# pro-micro-screw-terminal-v1_0.net
KiCad netlist of a schematic drawn in EAGLE
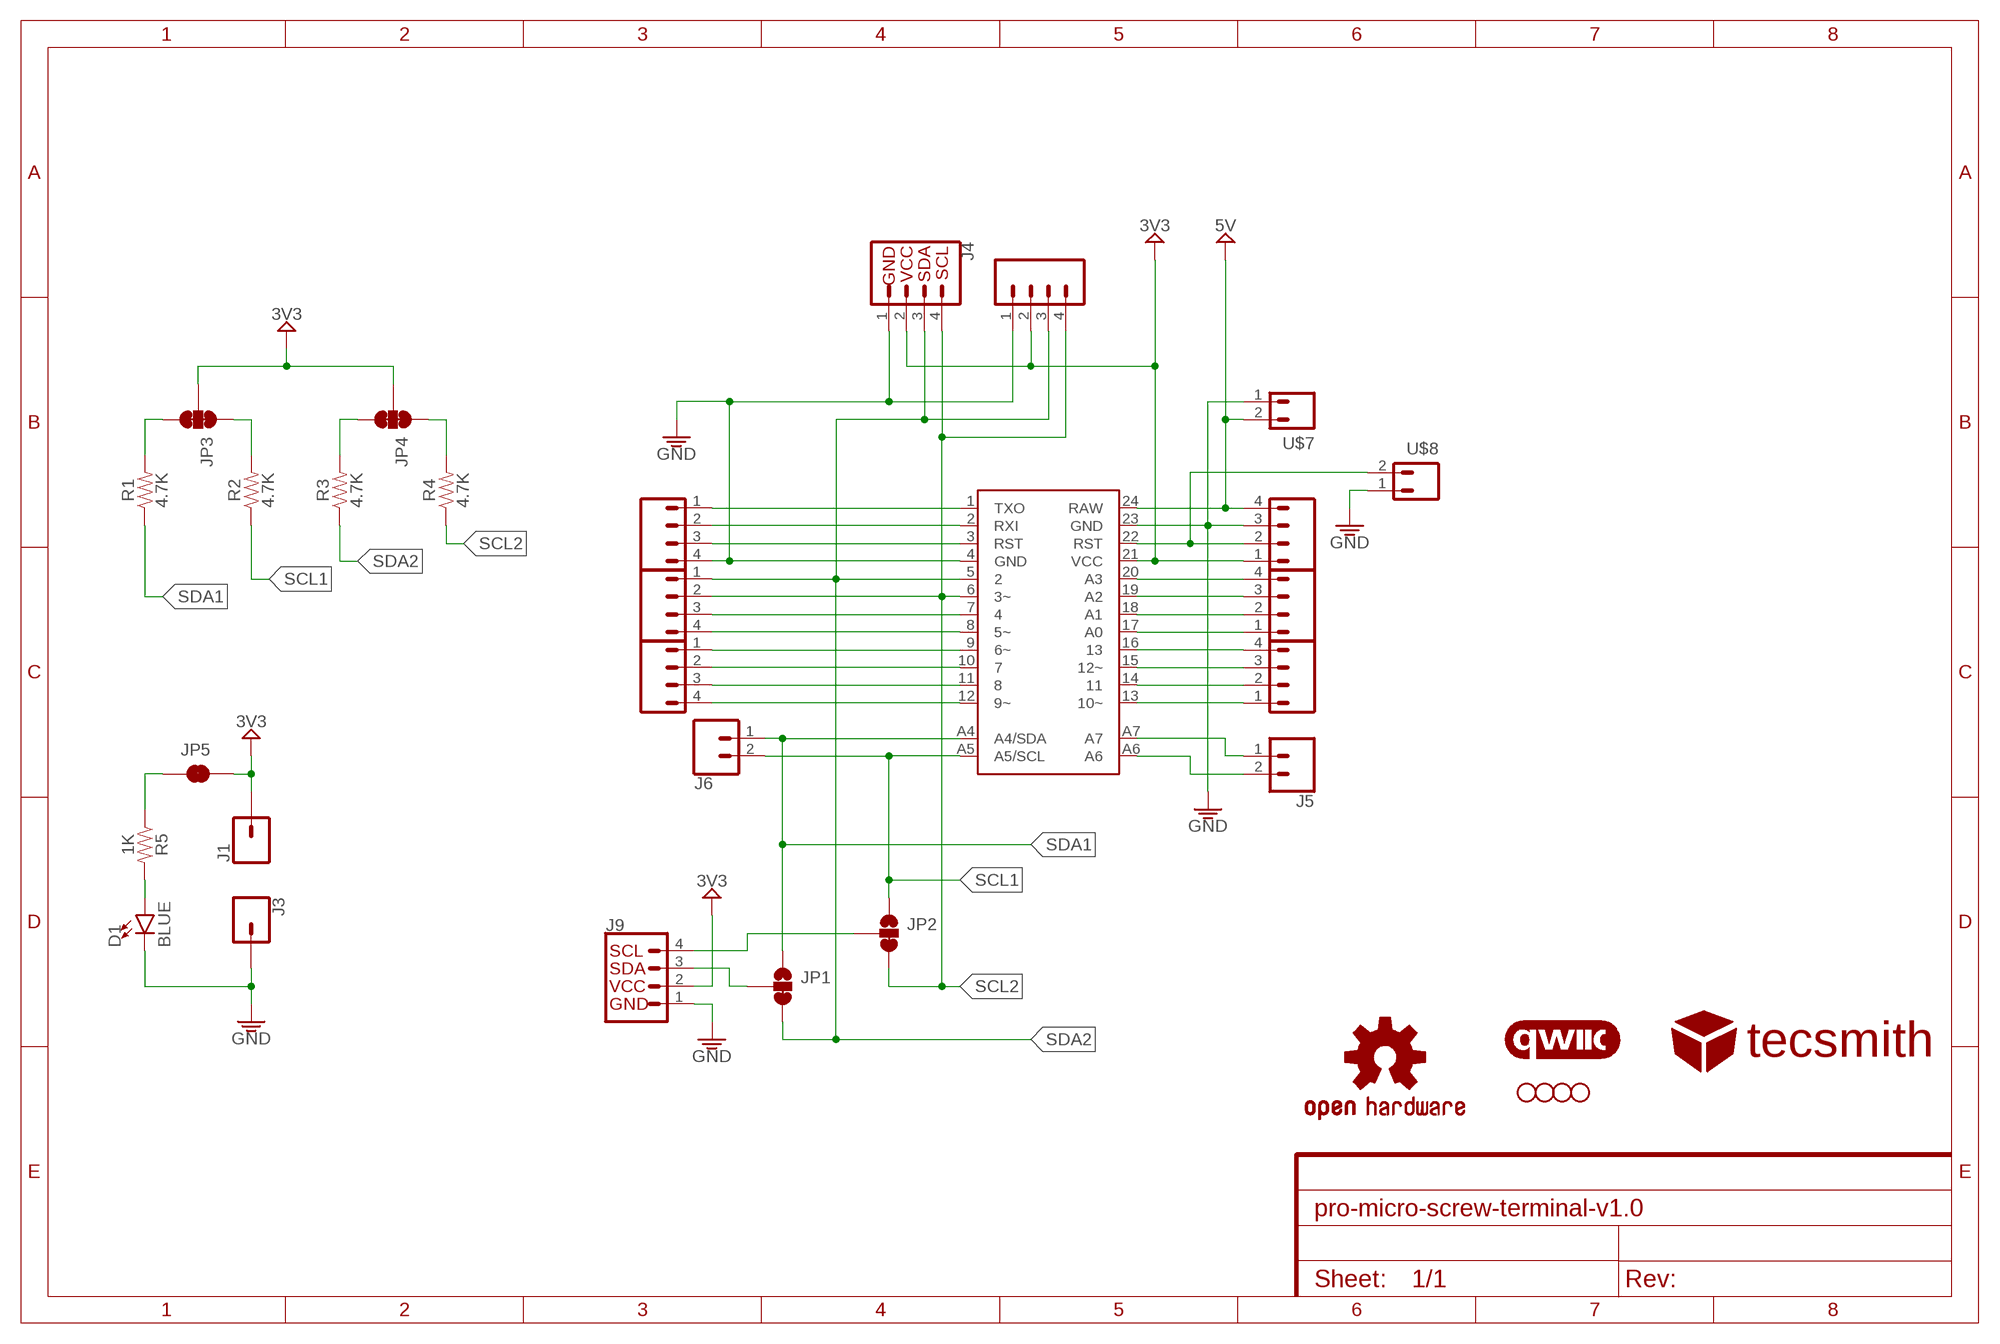
[diagram p0: schematic, sheet 1]

(export (version "E")
  (design (tool "Eeschema 10.0.6"))
  (components
    (comp (ref "B1")
      (value "ARDUINO_PRO_MININO_FTDI")
      (footprint "eagle-import:ARDUINO_PRO_MINI")
      (libsource (lib "eagle-import") (part "ARDUINO_PRO_MININO_FTDI"))
    )
    (comp (ref "D1")
      (value "BLUE")
      (footprint "eagle-import:LED-0603")
      (libsource (lib "eagle-import") (part "LED-BLUE0603"))
    )
    (comp (ref "H1")
      (value "STAND-OFF")
      (footprint "eagle-import:STAND-OFF")
      (libsource (lib "eagle-import") (part "STAND-OFF"))
    )
    (comp (ref "H2")
      (value "STAND-OFF")
      (footprint "eagle-import:STAND-OFF")
      (libsource (lib "eagle-import") (part "STAND-OFF"))
    )
    (comp (ref "H5")
      (value "STAND-OFF")
      (footprint "eagle-import:STAND-OFF")
      (libsource (lib "eagle-import") (part "STAND-OFF"))
    )
    (comp (ref "H6")
      (value "STAND-OFF")
      (footprint "eagle-import:STAND-OFF")
      (libsource (lib "eagle-import") (part "STAND-OFF"))
    )
    (comp (ref "J1")
      (value "CONN_01PTH_NO_SILK_YES_STOP")
      (footprint "eagle-import:1X01_NO_SILK")
      (libsource (lib "eagle-import") (part "CONN_01PTH_NO_SILK_YES_STOP"))
    )
    (comp (ref "J2")
      (value "CONN_04PTH")
      (footprint "eagle-import:1X04")
      (libsource (lib "eagle-import") (part "CONN_04PTH"))
    )
    (comp (ref "J3")
      (value "CONN_01PTH_NO_SILK_YES_STOP")
      (footprint "eagle-import:1X01_NO_SILK")
      (libsource (lib "eagle-import") (part "CONN_01PTH_NO_SILK_YES_STOP"))
    )
    (comp (ref "J4")
      (value "QWIIC_RIGHT_ANGLE")
      (footprint "eagle-import:JST04_1MM_RA")
      (libsource (lib "eagle-import") (part "QWIIC_CONNECTORJS-1MM"))
    )
    (comp (ref "J5")
      (value "CONN_02")
      (footprint "eagle-import:1X02")
      (libsource (lib "eagle-import") (part "CONN_02"))
    )
    (comp (ref "J6")
      (value "CONN_02")
      (footprint "eagle-import:1X02")
      (libsource (lib "eagle-import") (part "CONN_02"))
    )
    (comp (ref "J9")
      (value "QWIIC_RIGHT_ANGLE")
      (footprint "eagle-import:JST04_1MM_RA")
      (libsource (lib "eagle-import") (part "QWIIC_CONNECTORJS-1MM"))
    )
    (comp (ref "JP1")
      (value "JUMPER-SMT_3_1-NC_TRACE_SILK")
      (footprint "eagle-import:SMT-JUMPER_3_1-NC_TRACE_SILK")
      (libsource (lib "eagle-import") (part "JUMPER-SMT_3_1-NC_TRACE_SILK"))
    )
    (comp (ref "JP2")
      (value "JUMPER-SMT_3_1-NC_TRACE_SILK")
      (footprint "eagle-import:SMT-JUMPER_3_1-NC_TRACE_SILK")
      (libsource (lib "eagle-import") (part "JUMPER-SMT_3_1-NC_TRACE_SILK"))
    )
    (comp (ref "JP3")
      (value "JUMPER-SMT_3_2-NC_TRACE_SILK")
      (footprint "eagle-import:SMT-JUMPER_3_2-NC_TRACE_SILK")
      (libsource (lib "eagle-import") (part "JUMPER-SMT_3_2-NC_TRACE_SILK"))
    )
    (comp (ref "JP4")
      (value "JUMPER-SMT_3_2-NC_TRACE_SILK")
      (footprint "eagle-import:SMT-JUMPER_3_2-NC_TRACE_SILK")
      (libsource (lib "eagle-import") (part "JUMPER-SMT_3_2-NC_TRACE_SILK"))
    )
    (comp (ref "JP5")
      (value "JUMPER-SMT_2_NC_TRACE_SILK")
      (footprint "eagle-import:SMT-JUMPER_2_NC_TRACE_SILK")
      (libsource (lib "eagle-import") (part "JUMPER-SMT_2_NC_TRACE_SILK"))
    )
    (comp (ref "LOGO1")
      (value "OSHW-LOGOS")
      (footprint "eagle-import:OSHW-LOGO-S")
      (libsource (lib "eagle-import") (part "OSHW-LOGOS"))
    )
    (comp (ref "LOGO2")
      (value "QWIIC_LOGO_6MM")
      (footprint "eagle-import:QWIIC_6MM")
      (libsource (lib "eagle-import") (part "QWIIC_LOGO_6MM"))
    )
    (comp (ref "R1")
      (value "4.7K")
      (footprint "eagle-import:0805")
      (libsource (lib "eagle-import") (part "RESISTOR0805"))
    )
    (comp (ref "R2")
      (value "4.7K")
      (footprint "eagle-import:0805")
      (libsource (lib "eagle-import") (part "RESISTOR0805"))
    )
    (comp (ref "R3")
      (value "4.7K")
      (footprint "eagle-import:0805")
      (libsource (lib "eagle-import") (part "RESISTOR0805"))
    )
    (comp (ref "R4")
      (value "4.7K")
      (footprint "eagle-import:0805")
      (libsource (lib "eagle-import") (part "RESISTOR0805"))
    )
    (comp (ref "R5")
      (value "1K")
      (footprint "eagle-import:0603")
      (libsource (lib "eagle-import") (part "330OHM-0603-1/10W-1%"))
    )
    (comp (ref "U$1")
      (value "CON_04SCREW")
      (footprint "eagle-import:WURTH_2431_3.5MM_4X_SCREW")
      (libsource (lib "eagle-import") (part "CON_04SCREW"))
    )
    (comp (ref "U$2")
      (value "CON_04SCREW")
      (footprint "eagle-import:WURTH_2431_3.5MM_4X_SCREW")
      (libsource (lib "eagle-import") (part "CON_04SCREW"))
    )
    (comp (ref "U$3")
      (value "CON_04SCREW")
      (footprint "eagle-import:WURTH_2431_3.5MM_4X_SCREW")
      (libsource (lib "eagle-import") (part "CON_04SCREW"))
    )
    (comp (ref "U$4")
      (value "CON_04SCREW")
      (footprint "eagle-import:WURTH_2431_3.5MM_4X_SCREW")
      (libsource (lib "eagle-import") (part "CON_04SCREW"))
    )
    (comp (ref "U$5")
      (value "CON_04SCREW")
      (footprint "eagle-import:WURTH_2431_3.5MM_4X_SCREW")
      (libsource (lib "eagle-import") (part "CON_04SCREW"))
    )
    (comp (ref "U$6")
      (value "CON_04SCREW")
      (footprint "eagle-import:WURTH_2431_3.5MM_4X_SCREW")
      (libsource (lib "eagle-import") (part "CON_04SCREW"))
    )
    (comp (ref "U$7")
      (value "CON_02SCREW")
      (footprint "eagle-import:WURTH_2431_3.5MM_2X_SCREW")
      (libsource (lib "eagle-import") (part "CON_02SCREW"))
    )
    (comp (ref "U$8")
      (value "JST-PH-2NS")
      (footprint "eagle-import:JST-PH2-NO-SILK")
      (libsource (lib "eagle-import") (part "JST-PH-2NS"))
    )
    (comp (ref "U$9")
      (value "TECSMITH-LOGO")
      (footprint "eagle-import:TECSMITH-LOGO")
      (libsource (lib "eagle-import") (part "TECSMITH-LOGO"))
    )
  )
  (nets
    (net (code "1") (name "3V3") (class "Default")
      (node (ref "B1") (pin "21") (pinfunction "VCC_21") (pintype "power_in"))
      (node (ref "J1") (pin "1") (pinfunction "1_1") (pintype "passive"))
      (node (ref "J2") (pin "2") (pinfunction "2_2") (pintype "passive"))
      (node (ref "J4") (pin "2") (pinfunction "2_2") (pintype "power_in"))
      (node (ref "J9") (pin "2") (pinfunction "2_2") (pintype "power_in"))
      (node (ref "JP3") (pin "2") (pinfunction "2_2") (pintype "passive"))
      (node (ref "JP4") (pin "2") (pinfunction "2_2") (pintype "passive"))
      (node (ref "JP5") (pin "2") (pinfunction "2_2") (pintype "passive"))
      (node (ref "U$6") (pin "1") (pinfunction "1_1") (pintype "passive"))
    )
    (net (code "2") (name "5V") (class "Default")
      (node (ref "B1") (pin "24") (pinfunction "RAW_24") (pintype "power_in"))
      (node (ref "U$6") (pin "4") (pinfunction "4_4") (pintype "passive"))
      (node (ref "U$7") (pin "2") (pinfunction "2_2") (pintype "passive"))
    )
    (net (code "3") (name "GND") (class "Default")
      (node (ref "B1") (pin "23") (pinfunction "GND_23") (pintype "power_in"))
      (node (ref "B1") (pin "4") (pinfunction "GND_4") (pintype "power_in"))
      (node (ref "D1") (pin "C") (pinfunction "C_C") (pintype "passive"))
      (node (ref "J2") (pin "1") (pinfunction "1_1") (pintype "passive"))
      (node (ref "J3") (pin "1") (pinfunction "1_1") (pintype "passive"))
      (node (ref "J4") (pin "1") (pinfunction "1_1") (pintype "power_in"))
      (node (ref "J9") (pin "1") (pinfunction "1_1") (pintype "power_in"))
      (node (ref "U$1") (pin "4") (pinfunction "4_4") (pintype "passive"))
      (node (ref "U$6") (pin "3") (pinfunction "3_3") (pintype "passive"))
      (node (ref "U$7") (pin "1") (pinfunction "1_1") (pintype "passive"))
      (node (ref "U$8") (pin "1") (pinfunction "1_1") (pintype "passive"))
    )
    (net (code "4") (name "Net-(B1-4)") (class "Default")
      (node (ref "B1") (pin "7") (pinfunction "4_7") (pintype "bidirectional"))
      (node (ref "U$2") (pin "3") (pinfunction "3_3") (pintype "passive"))
    )
    (net (code "5") (name "Net-(B1-5~{})") (class "Default")
      (node (ref "B1") (pin "8") (pinfunction "5~{}_8") (pintype "bidirectional"))
      (node (ref "U$2") (pin "4") (pinfunction "4_4") (pintype "passive"))
    )
    (net (code "6") (name "Net-(B1-6~{})") (class "Default")
      (node (ref "B1") (pin "9") (pinfunction "6~{}_9") (pintype "bidirectional"))
      (node (ref "U$3") (pin "1") (pinfunction "1_1") (pintype "passive"))
    )
    (net (code "7") (name "Net-(B1-7)") (class "Default")
      (node (ref "B1") (pin "10") (pinfunction "7_10") (pintype "bidirectional"))
      (node (ref "U$3") (pin "2") (pinfunction "2_2") (pintype "passive"))
    )
    (net (code "8") (name "Net-(B1-8)") (class "Default")
      (node (ref "B1") (pin "11") (pinfunction "8_11") (pintype "bidirectional"))
      (node (ref "U$3") (pin "3") (pinfunction "3_3") (pintype "passive"))
    )
    (net (code "9") (name "Net-(B1-9~{})") (class "Default")
      (node (ref "B1") (pin "12") (pinfunction "9~{}_12") (pintype "bidirectional"))
      (node (ref "U$3") (pin "4") (pinfunction "4_4") (pintype "passive"))
    )
    (net (code "10") (name "Net-(B1-10~{})") (class "Default")
      (node (ref "B1") (pin "13") (pinfunction "10~{}_13") (pintype "bidirectional"))
      (node (ref "U$4") (pin "1") (pinfunction "1_1") (pintype "passive"))
    )
    (net (code "11") (name "Net-(B1-11)") (class "Default")
      (node (ref "B1") (pin "14") (pinfunction "11_14") (pintype "bidirectional"))
      (node (ref "U$4") (pin "2") (pinfunction "2_2") (pintype "passive"))
    )
    (net (code "12") (name "Net-(B1-12~{})") (class "Default")
      (node (ref "B1") (pin "15") (pinfunction "12~{}_15") (pintype "bidirectional"))
      (node (ref "U$4") (pin "3") (pinfunction "3_3") (pintype "passive"))
    )
    (net (code "13") (name "Net-(B1-13)") (class "Default")
      (node (ref "B1") (pin "16") (pinfunction "13_16") (pintype "bidirectional"))
      (node (ref "U$4") (pin "4") (pinfunction "4_4") (pintype "passive"))
    )
    (net (code "14") (name "Net-(B1-A0)") (class "Default")
      (node (ref "B1") (pin "17") (pinfunction "A0_17") (pintype "bidirectional"))
      (node (ref "U$5") (pin "1") (pinfunction "1_1") (pintype "passive"))
    )
    (net (code "15") (name "Net-(B1-A1)") (class "Default")
      (node (ref "B1") (pin "18") (pinfunction "A1_18") (pintype "bidirectional"))
      (node (ref "U$5") (pin "2") (pinfunction "2_2") (pintype "passive"))
    )
    (net (code "16") (name "Net-(B1-A2)") (class "Default")
      (node (ref "B1") (pin "19") (pinfunction "A2_19") (pintype "bidirectional"))
      (node (ref "U$5") (pin "3") (pinfunction "3_3") (pintype "passive"))
    )
    (net (code "17") (name "Net-(B1-A3)") (class "Default")
      (node (ref "B1") (pin "20") (pinfunction "A3_20") (pintype "bidirectional"))
      (node (ref "U$5") (pin "4") (pinfunction "4_4") (pintype "passive"))
    )
    (net (code "18") (name "Net-(B1-PadA6)") (class "Default")
      (node (ref "B1") (pin "A6") (pinfunction "A6_A6") (pintype "bidirectional"))
      (node (ref "J5") (pin "2") (pinfunction "2_2") (pintype "passive"))
    )
    (net (code "19") (name "Net-(B1-PadA7)") (class "Default")
      (node (ref "B1") (pin "A7") (pinfunction "A7_A7") (pintype "bidirectional"))
      (node (ref "J5") (pin "1") (pinfunction "1_1") (pintype "passive"))
    )
    (net (code "20") (name "Net-(B1-RST-Pad3)") (class "Default")
      (node (ref "B1") (pin "3") (pinfunction "RST_3") (pintype "bidirectional"))
      (node (ref "U$1") (pin "3") (pinfunction "3_3") (pintype "passive"))
    )
    (net (code "21") (name "Net-(B1-RST-Pad22)") (class "Default")
      (node (ref "B1") (pin "22") (pinfunction "RST_22") (pintype "bidirectional"))
      (node (ref "U$6") (pin "2") (pinfunction "2_2") (pintype "passive"))
      (node (ref "U$8") (pin "2") (pinfunction "2_2") (pintype "passive"))
    )
    (net (code "22") (name "Net-(B1-RXI)") (class "Default")
      (node (ref "B1") (pin "2") (pinfunction "RXI_2") (pintype "bidirectional"))
      (node (ref "U$1") (pin "2") (pinfunction "2_2") (pintype "passive"))
    )
    (net (code "23") (name "Net-(B1-TXO)") (class "Default")
      (node (ref "B1") (pin "1") (pinfunction "TXO_1") (pintype "bidirectional"))
      (node (ref "U$1") (pin "1") (pinfunction "1_1") (pintype "passive"))
    )
    (net (code "24") (name "Net-(D1-PadA)") (class "Default")
      (node (ref "D1") (pin "A") (pinfunction "A_A") (pintype "passive"))
      (node (ref "R5") (pin "2") (pinfunction "2_2") (pintype "passive"))
    )
    (net (code "25") (name "Net-(J9-Pad3)") (class "Default")
      (node (ref "J9") (pin "3") (pinfunction "3_3") (pintype "passive"))
      (node (ref "JP1") (pin "2") (pinfunction "2_2") (pintype "passive"))
    )
    (net (code "26") (name "Net-(J9-Pad4)") (class "Default")
      (node (ref "J9") (pin "4") (pinfunction "4_4") (pintype "passive"))
      (node (ref "JP2") (pin "2") (pinfunction "2_2") (pintype "passive"))
    )
    (net (code "27") (name "Net-(JP3-Pad1)") (class "Default")
      (node (ref "JP3") (pin "1") (pinfunction "1_1") (pintype "passive"))
      (node (ref "R2") (pin "2") (pinfunction "2_2") (pintype "passive"))
    )
    (net (code "28") (name "Net-(JP3-Pad3)") (class "Default")
      (node (ref "JP3") (pin "3") (pinfunction "3_3") (pintype "passive"))
      (node (ref "R1") (pin "2") (pinfunction "2_2") (pintype "passive"))
    )
    (net (code "29") (name "Net-(JP4-Pad1)") (class "Default")
      (node (ref "JP4") (pin "1") (pinfunction "1_1") (pintype "passive"))
      (node (ref "R4") (pin "2") (pinfunction "2_2") (pintype "passive"))
    )
    (net (code "30") (name "Net-(JP4-Pad3)") (class "Default")
      (node (ref "JP4") (pin "3") (pinfunction "3_3") (pintype "passive"))
      (node (ref "R3") (pin "2") (pinfunction "2_2") (pintype "passive"))
    )
    (net (code "31") (name "Net-(JP5-Pad1)") (class "Default")
      (node (ref "JP5") (pin "1") (pinfunction "1_1") (pintype "passive"))
      (node (ref "R5") (pin "1") (pinfunction "1_1") (pintype "passive"))
    )
    (net (code "32") (name "SCL1") (class "Default")
      (node (ref "B1") (pin "A5") (pinfunction "A5/SCL_A5") (pintype "bidirectional"))
      (node (ref "J6") (pin "2") (pinfunction "2_2") (pintype "passive"))
      (node (ref "JP2") (pin "1") (pinfunction "1_1") (pintype "passive"))
      (node (ref "R2") (pin "1") (pinfunction "1_1") (pintype "passive"))
    )
    (net (code "33") (name "SCL2") (class "Default")
      (node (ref "B1") (pin "6") (pinfunction "3~{}_6") (pintype "bidirectional"))
      (node (ref "J2") (pin "4") (pinfunction "4_4") (pintype "passive"))
      (node (ref "J4") (pin "4") (pinfunction "4_4") (pintype "passive"))
      (node (ref "JP2") (pin "3") (pinfunction "3_3") (pintype "passive"))
      (node (ref "R4") (pin "1") (pinfunction "1_1") (pintype "passive"))
      (node (ref "U$2") (pin "2") (pinfunction "2_2") (pintype "passive"))
    )
    (net (code "34") (name "SDA1") (class "Default")
      (node (ref "B1") (pin "A4") (pinfunction "A4/SDA_A4") (pintype "bidirectional"))
      (node (ref "J6") (pin "1") (pinfunction "1_1") (pintype "passive"))
      (node (ref "JP1") (pin "1") (pinfunction "1_1") (pintype "passive"))
      (node (ref "R1") (pin "1") (pinfunction "1_1") (pintype "passive"))
    )
    (net (code "35") (name "SDA2") (class "Default")
      (node (ref "B1") (pin "5") (pinfunction "2_5") (pintype "bidirectional"))
      (node (ref "J2") (pin "3") (pinfunction "3_3") (pintype "passive"))
      (node (ref "J4") (pin "3") (pinfunction "3_3") (pintype "passive"))
      (node (ref "JP1") (pin "3") (pinfunction "3_3") (pintype "passive"))
      (node (ref "R3") (pin "1") (pinfunction "1_1") (pintype "passive"))
      (node (ref "U$2") (pin "1") (pinfunction "1_1") (pintype "passive"))
    )
  )
)
